# Clock_V1_0_0.net
KiCad netlist of a schematic drawn in EasyEDA Pro
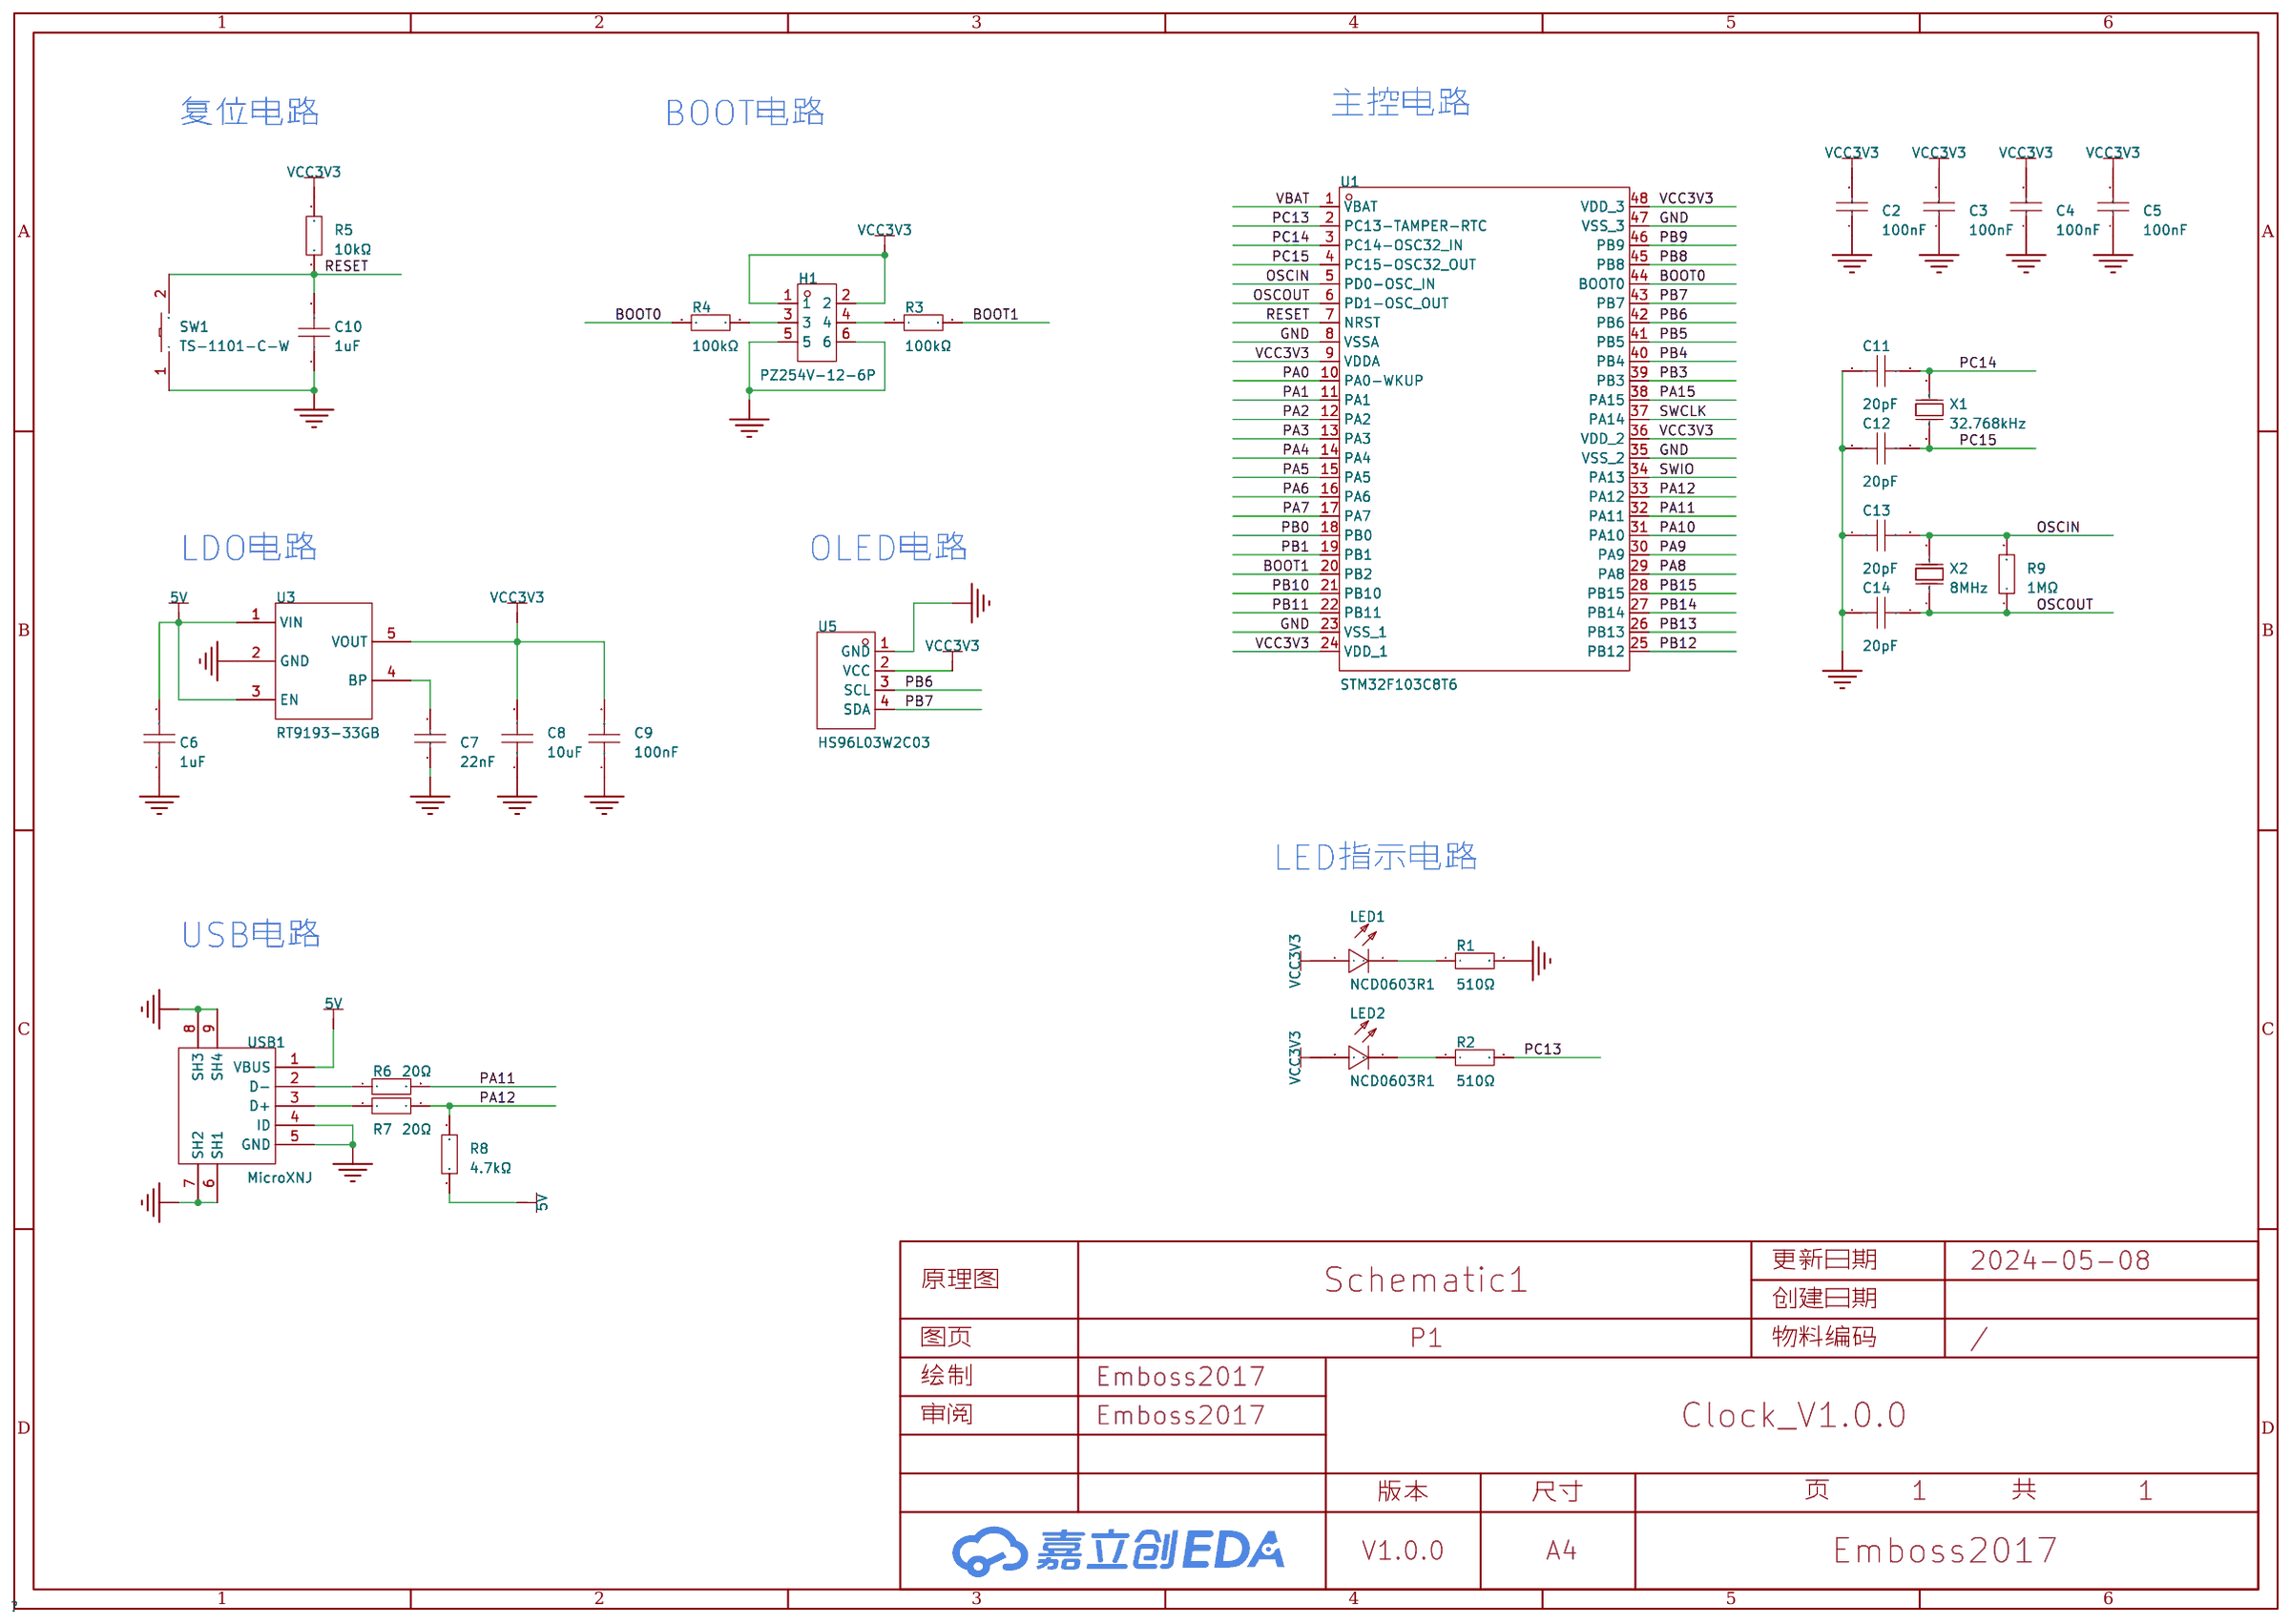
[diagram p0: schematic sheet]

(export (version "E")
  (design (tool "Eeschema 10.0.6"))
  (components
    (comp (ref "C2")
      (value "100nF")
      (footprint "easyedapro:C0603")
      (description "容值:100nF;精度:±10%;额定电压:50V;材质(温度系数):X7R;")
      (fields (field (name "Manufacturer Part") "0603B104K500NT") (field (name "Manufacturer") "FH(风华)"))
      (libsource (lib "easyedapro") (part "0603B104K500NT"))
    )
    (comp (ref "C3")
      (value "100nF")
      (footprint "easyedapro:C0603")
      (description "容值:100nF;精度:±10%;额定电压:50V;材质(温度系数):X7R;")
      (fields (field (name "Manufacturer Part") "0603B104K500NT") (field (name "Manufacturer") "FH(风华)"))
      (libsource (lib "easyedapro") (part "0603B104K500NT"))
    )
    (comp (ref "C4")
      (value "100nF")
      (footprint "easyedapro:C0603")
      (description "容值:100nF;精度:±10%;额定电压:50V;材质(温度系数):X7R;")
      (fields (field (name "Manufacturer Part") "0603B104K500NT") (field (name "Manufacturer") "FH(风华)"))
      (libsource (lib "easyedapro") (part "0603B104K500NT"))
    )
    (comp (ref "C5")
      (value "100nF")
      (footprint "easyedapro:C0603")
      (description "容值:100nF;精度:±10%;额定电压:50V;材质(温度系数):X7R;")
      (fields (field (name "Manufacturer Part") "0603B104K500NT") (field (name "Manufacturer") "FH(风华)"))
      (libsource (lib "easyedapro") (part "0603B104K500NT"))
    )
    (comp (ref "C6")
      (value "1uF")
      (footprint "easyedapro:C0603")
      (description "容值:-;额定电压:-;材质(温度系数):-;")
      (fields (field (name "Manufacturer Part") "1uF(105) ±10% 25V"))
      (libsource (lib "easyedapro") (part "1UF(105)-±10%-25V"))
    )
    (comp (ref "C7")
      (value "22nF")
      (footprint "easyedapro:C0603")
      (description "容值:22nF;精度:±10%;额定电压:50V;材质(温度系数):X7R;")
      (fields
        (field (name "Manufacturer Part") "CL10B223KB8NNNC")
        (field (name "Manufacturer") "SAMSUNG(三星)")
      )
      (libsource (lib "easyedapro") (part "CL10B223KB8NNNC"))
    )
    (comp (ref "C8")
      (value "10uF")
      (footprint "easyedapro:C0603")
      (description "容值:10uF;精度:±10%;额定电压:10V;材质(温度系数):X5R;")
      (fields
        (field (name "Manufacturer Part") "CL10A106KP8NNNC")
        (field (name "Manufacturer") "SAMSUNG(三星)")
      )
      (libsource (lib "easyedapro") (part "CL10A106KP8NNNC"))
    )
    (comp (ref "C9")
      (value "100nF")
      (footprint "easyedapro:C0603")
      (description "容值:100nF;精度:±10%;额定电压:50V;材质(温度系数):X7R;")
      (fields
        (field (name "Manufacturer Part") "CC0603KRX7R9BB104")
        (field (name "Manufacturer") "YAGEO(国巨)")
      )
      (libsource (lib "easyedapro") (part "CC0603KRX7R9BB104"))
    )
    (comp (ref "C10")
      (value "1uF")
      (footprint "easyedapro:C0603")
      (description "容值:-;额定电压:-;材质(温度系数):-;")
      (fields (field (name "Manufacturer Part") "1uF(105) ±10% 25V"))
      (libsource (lib "easyedapro") (part "1UF(105)-±10%-25V"))
    )
    (comp (ref "C11")
      (value "20pF")
      (footprint "easyedapro:C0603")
      (description "容值:20pF;精度:±5%;额定电压:50V;材质(温度系数):C0G;")
      (fields (field (name "Manufacturer Part") "0603CG200J500NT") (field (name "Manufacturer") "FH(风华)"))
      (libsource (lib "easyedapro") (part "0603CG200J500NT"))
    )
    (comp (ref "C12")
      (value "20pF")
      (footprint "easyedapro:C0603")
      (description "容值:20pF;精度:±5%;额定电压:50V;材质(温度系数):C0G;")
      (fields (field (name "Manufacturer Part") "0603CG200J500NT") (field (name "Manufacturer") "FH(风华)"))
      (libsource (lib "easyedapro") (part "0603CG200J500NT"))
    )
    (comp (ref "C13")
      (value "20pF")
      (footprint "easyedapro:C0603")
      (description "容值:20pF;精度:±5%;额定电压:50V;材质(温度系数):C0G;")
      (fields (field (name "Manufacturer Part") "0603CG200J500NT") (field (name "Manufacturer") "FH(风华)"))
      (libsource (lib "easyedapro") (part "0603CG200J500NT"))
    )
    (comp (ref "C14")
      (value "20pF")
      (footprint "easyedapro:C0603")
      (description "容值:20pF;精度:±5%;额定电压:50V;材质(温度系数):C0G;")
      (fields (field (name "Manufacturer Part") "0603CG200J500NT") (field (name "Manufacturer") "FH(风华)"))
      (libsource (lib "easyedapro") (part "0603CG200J500NT"))
    )
    (comp (ref "H1")
      (value "PZ254V-12-6P")
      (footprint "easyedapro:HDR-TH_6P-P2.54-V-M-R2-C3-S2.54")
      (fields (field (name "Manufacturer") "XFCN(兴飞)"))
      (libsource (lib "easyedapro") (part "PZ254V-12-6P"))
    )
    (comp (ref "LED1")
      (value "NCD0603R1")
      (footprint "easyedapro:LED0603-RD_RED")
      (fields (field (name "Manufacturer") "国星光电"))
      (libsource (lib "easyedapro") (part "FC-DA1608HRK-620D"))
    )
    (comp (ref "LED2")
      (value "NCD0603R1")
      (footprint "easyedapro:LED0603-RD_RED")
      (fields (field (name "Manufacturer") "国星光电"))
      (libsource (lib "easyedapro") (part "FC-DA1608HRK-620D"))
    )
    (comp (ref "R1")
      (value "510Ω")
      (footprint "easyedapro:R0603")
      (description "电阻类型:厚膜电阻;阻值:510Ω;精度:±1%;功率:100mW;最大工作电压:75V;温度系数:±100ppm/°C;")
      (fields
        (field (name "Manufacturer Part") "0603WAF5100T5E")
        (field (name "Manufacturer") "UNI-ROYAL(厚声)")
      )
      (libsource (lib "easyedapro") (part "0603WAF5100T5E"))
    )
    (comp (ref "R2")
      (value "510Ω")
      (footprint "easyedapro:R0603")
      (description "电阻类型:厚膜电阻;阻值:510Ω;精度:±1%;功率:100mW;最大工作电压:75V;温度系数:±100ppm/°C;")
      (fields
        (field (name "Manufacturer Part") "0603WAF5100T5E")
        (field (name "Manufacturer") "UNI-ROYAL(厚声)")
      )
      (libsource (lib "easyedapro") (part "0603WAF5100T5E"))
    )
    (comp (ref "R3")
      (value "100kΩ")
      (footprint "easyedapro:R0603")
      (description "电阻类型:厚膜电阻;阻值:100kΩ;精度:±1%;功率:100mW;最大工作电压:75V;温度系数:±100ppm/°C;")
      (fields
        (field (name "Manufacturer Part") "0603WAF1003T5E")
        (field (name "Manufacturer") "UNI-ROYAL(厚声)")
      )
      (libsource (lib "easyedapro") (part "0603WAF1003T5E"))
    )
    (comp (ref "R4")
      (value "100kΩ")
      (footprint "easyedapro:R0603")
      (description "电阻类型:厚膜电阻;阻值:100kΩ;精度:±1%;功率:100mW;最大工作电压:75V;温度系数:±100ppm/°C;")
      (fields
        (field (name "Manufacturer Part") "0603WAF1003T5E")
        (field (name "Manufacturer") "UNI-ROYAL(厚声)")
      )
      (libsource (lib "easyedapro") (part "0603WAF1003T5E"))
    )
    (comp (ref "R5")
      (value "10kΩ")
      (footprint "easyedapro:R0603")
      (description "电阻类型:厚膜电阻;阻值:10kΩ;精度:±1%;功率:100mW;最大工作电压:75V;温度系数:±100ppm/°C;")
      (fields
        (field (name "Manufacturer Part") "0603WAF1002T5E")
        (field (name "Manufacturer") "UNI-ROYAL(厚声)")
      )
      (libsource (lib "easyedapro") (part "0603WAF1002T5E"))
    )
    (comp (ref "R6")
      (value "20Ω")
      (footprint "easyedapro:R1206")
      (description "电阻类型:厚膜电阻;阻值:20Ω;精度:±1%;功率:250mW;最大工作电压:200V;温度系数:±100ppm/°C;")
      (fields
        (field (name "Manufacturer Part") "1206W4F200JT5E")
        (field (name "Manufacturer") "UNI-ROYAL(厚声)")
      )
      (libsource (lib "easyedapro") (part "1206W4F200JT5E"))
    )
    (comp (ref "R7")
      (value "20Ω")
      (footprint "easyedapro:R1206")
      (description "电阻类型:厚膜电阻;阻值:20Ω;精度:±1%;功率:250mW;最大工作电压:200V;温度系数:±100ppm/°C;")
      (fields
        (field (name "Manufacturer Part") "1206W4F200JT5E")
        (field (name "Manufacturer") "UNI-ROYAL(厚声)")
      )
      (libsource (lib "easyedapro") (part "1206W4F200JT5E"))
    )
    (comp (ref "R8")
      (value "4.7kΩ")
      (footprint "easyedapro:R0603")
      (description "电阻类型:厚膜电阻;阻值:4.7kΩ;精度:±1%;功率:100mW;最大工作电压:75V;温度系数:±100ppm/°C;")
      (fields
        (field (name "Manufacturer Part") "0603WAF4701T5E")
        (field (name "Manufacturer") "UNI-ROYAL(厚声)")
      )
      (libsource (lib "easyedapro") (part "0603WAF4701T5E"))
    )
    (comp (ref "R9")
      (value "1MΩ")
      (footprint "easyedapro:R0603")
      (description "电阻类型:厚膜电阻;阻值:1MΩ;精度:±1%;功率:100mW;最大工作电压:75V;温度系数:±100ppm/°C;")
      (fields
        (field (name "Manufacturer Part") "0603WAF1004T5E")
        (field (name "Manufacturer") "UNI-ROYAL(厚声)")
      )
      (libsource (lib "easyedapro") (part "0603WAF1004T5E"))
    )
    (comp (ref "SW1")
      (value "TS-1101-C-W")
      (footprint "easyedapro:SW-SMD_L6.0-W3.3-LS8.0")
      (fields (field (name "Manufacturer") "XKB Connectivity(中国星坤)"))
      (libsource (lib "easyedapro") (part "TS-1101-C-W"))
    )
    (comp (ref "U1")
      (value "STM32F103C8T6")
      (footprint "easyedapro:LQFP-48_L7.0-W7.0-P0.50-LS9.0-BL")
      (description "CPU内核:CM3;程序存储容量:64KB;RAM总容量:20KB;GPIO端口数量:37;工作电压范围:2V~3.6V;CPU最大主频:72MHz;程序存储器类型:FLASH;")
      (fields (field (name "Manufacturer") "ST(意法半导体)"))
      (libsource (lib "easyedapro") (part "STM32F103C8T6"))
    )
    (comp (ref "U3")
      (value "RT9193-33GB")
      (footprint "easyedapro:SOT-23-5_L3.0-W1.7-P0.95-LS2.8-BL")
      (description "输出类型:固定;最大输入电压:5.5V;输出电压:3.3V;最大输出电流:300mA;电源纹波抑制比(PSRR):70dB;输出极性:正极;")
      (fields (field (name "Manufacturer") "RICHTEK(立锜)"))
      (libsource (lib "easyedapro") (part "RT9193-33GB"))
    )
    (comp (ref "U5")
      (value "HS96L03W2C03")
      (footprint "easyedapro:OLED-TH_L27.8-W27.2-P2.54_C9900033791")
      (description "主控芯片:SSD1315;接口类型:I2C;尺寸(inch):0.96;像素分辨率:128x64;")
      (fields (field (name "Manufacturer") "HS(汉昇)"))
      (libsource (lib "easyedapro") (part "HS96L03W2C03"))
    )
    (comp (ref "USB1")
      (value "MicroXNJ")
      (footprint "easyedapro:MICRO-USB-SMD_MICROXNJ")
      (description "连接器类型:Micro-B;标准:USB 2.0;公母:母;端口数量:1;触点数量:5P;安装方式:卧贴;额定电流 - 电源:1A;工作温度范围:-20°C~+85°C;")
      (fields (field (name "Manufacturer") "SHOU HAN(首韩)"))
      (libsource (lib "easyedapro") (part "MICROXNJ"))
    )
    (comp (ref "X1")
      (value "32.768kHz")
      (footprint "easyedapro:OSC-TH_BD2.0-P0.70-D0.3")
      (description "晶振类型:-;频率:-;外接负载电容:-;")
      (fields (field (name "Manufacturer Part") "DT-26 32.768KHz") (field (name "Manufacturer") "KDS(大真空)"))
      (libsource (lib "easyedapro") (part "DT-26 32.768KHz"))
    )
    (comp (ref "X2")
      (value "8MHz")
      (footprint "easyedapro:CRYSTAL-SMD_L11.5-W4.8-LS12.7")
      (description "晶振类型:贴片晶振;频率:8MHz;常温频差:±20ppm;外接负载电容:20pF;频率稳定度(全温):±30ppm;")
      (fields (field (name "Manufacturer Part") "X49SM8MSD2SC") (field (name "Manufacturer") "YXC(扬兴晶振)"))
      (libsource (lib "easyedapro") (part "X49SM8MSD2SC"))
    )
  )
  (nets
    (net (code "1") (name "/BOOT0") (class "Default")
      (node (ref "R4") (pin "1") (pinfunction "1_1") (pintype "input"))
      (node (ref "U1") (pin "44") (pinfunction "BOOT0_44") (pintype "unspecified"))
    )
    (net (code "2") (name "/BOOT1") (class "Default")
      (node (ref "R3") (pin "2") (pinfunction "2_2") (pintype "input"))
      (node (ref "U1") (pin "20") (pinfunction "PB2_20") (pintype "unspecified"))
    )
    (net (code "3") (name "/OSCIN") (class "Default")
      (node (ref "C13") (pin "2") (pinfunction "2_2") (pintype "unspecified"))
      (node (ref "R9") (pin "2") (pinfunction "2_2") (pintype "input"))
      (node (ref "U1") (pin "5") (pinfunction "PD0-OSC_IN_5") (pintype "unspecified"))
      (node (ref "X2") (pin "2") (pinfunction "OSC2_2") (pintype "input"))
    )
    (net (code "4") (name "/OSCOUT") (class "Default")
      (node (ref "C14") (pin "2") (pinfunction "2_2") (pintype "unspecified"))
      (node (ref "R9") (pin "1") (pinfunction "1_1") (pintype "input"))
      (node (ref "U1") (pin "6") (pinfunction "PD1-OSC_OUT_6") (pintype "unspecified"))
      (node (ref "X2") (pin "1") (pinfunction "OSC1_1") (pintype "input"))
    )
    (net (code "5") (name "/PA0") (class "Default")
      (node (ref "U1") (pin "10") (pinfunction "PA0-WKUP_10") (pintype "unspecified"))
    )
    (net (code "6") (name "/PA1") (class "Default")
      (node (ref "U1") (pin "11") (pinfunction "PA1_11") (pintype "unspecified"))
    )
    (net (code "7") (name "/PA2") (class "Default")
      (node (ref "U1") (pin "12") (pinfunction "PA2_12") (pintype "unspecified"))
    )
    (net (code "8") (name "/PA3") (class "Default")
      (node (ref "U1") (pin "13") (pinfunction "PA3_13") (pintype "unspecified"))
    )
    (net (code "9") (name "/PA4") (class "Default")
      (node (ref "U1") (pin "14") (pinfunction "PA4_14") (pintype "unspecified"))
    )
    (net (code "10") (name "/PA5") (class "Default")
      (node (ref "U1") (pin "15") (pinfunction "PA5_15") (pintype "unspecified"))
    )
    (net (code "11") (name "/PA6") (class "Default")
      (node (ref "U1") (pin "16") (pinfunction "PA6_16") (pintype "unspecified"))
    )
    (net (code "12") (name "/PA7") (class "Default")
      (node (ref "U1") (pin "17") (pinfunction "PA7_17") (pintype "unspecified"))
    )
    (net (code "13") (name "/PA8") (class "Default")
      (node (ref "U1") (pin "29") (pinfunction "PA8_29") (pintype "unspecified"))
    )
    (net (code "14") (name "/PA9") (class "Default")
      (node (ref "U1") (pin "30") (pinfunction "PA9_30") (pintype "unspecified"))
    )
    (net (code "15") (name "/PA10") (class "Default")
      (node (ref "U1") (pin "31") (pinfunction "PA10_31") (pintype "unspecified"))
    )
    (net (code "16") (name "/PA11") (class "Default")
      (node (ref "R6") (pin "2") (pinfunction "2_2") (pintype "input"))
      (node (ref "U1") (pin "32") (pinfunction "PA11_32") (pintype "unspecified"))
    )
    (net (code "17") (name "/PA12") (class "Default")
      (node (ref "R7") (pin "2") (pinfunction "2_2") (pintype "input"))
      (node (ref "R8") (pin "2") (pinfunction "2_2") (pintype "input"))
      (node (ref "U1") (pin "33") (pinfunction "PA12_33") (pintype "unspecified"))
    )
    (net (code "18") (name "/PA15") (class "Default")
      (node (ref "U1") (pin "38") (pinfunction "PA15_38") (pintype "unspecified"))
    )
    (net (code "19") (name "/PB0") (class "Default")
      (node (ref "U1") (pin "18") (pinfunction "PB0_18") (pintype "unspecified"))
    )
    (net (code "20") (name "/PB1") (class "Default")
      (node (ref "U1") (pin "19") (pinfunction "PB1_19") (pintype "unspecified"))
    )
    (net (code "21") (name "/PB3") (class "Default")
      (node (ref "U1") (pin "39") (pinfunction "PB3_39") (pintype "unspecified"))
    )
    (net (code "22") (name "/PB4") (class "Default")
      (node (ref "U1") (pin "40") (pinfunction "PB4_40") (pintype "unspecified"))
    )
    (net (code "23") (name "/PB5") (class "Default")
      (node (ref "U1") (pin "41") (pinfunction "PB5_41") (pintype "unspecified"))
    )
    (net (code "24") (name "/PB6") (class "Default")
      (node (ref "U1") (pin "42") (pinfunction "PB6_42") (pintype "unspecified"))
      (node (ref "U5") (pin "3") (pinfunction "SCL_3") (pintype "unspecified"))
    )
    (net (code "25") (name "/PB7") (class "Default")
      (node (ref "U1") (pin "43") (pinfunction "PB7_43") (pintype "unspecified"))
      (node (ref "U5") (pin "4") (pinfunction "SDA_4") (pintype "unspecified"))
    )
    (net (code "26") (name "/PB8") (class "Default")
      (node (ref "U1") (pin "45") (pinfunction "PB8_45") (pintype "unspecified"))
    )
    (net (code "27") (name "/PB9") (class "Default")
      (node (ref "U1") (pin "46") (pinfunction "PB9_46") (pintype "unspecified"))
    )
    (net (code "28") (name "/PB10") (class "Default")
      (node (ref "U1") (pin "21") (pinfunction "PB10_21") (pintype "unspecified"))
    )
    (net (code "29") (name "/PB11") (class "Default")
      (node (ref "U1") (pin "22") (pinfunction "PB11_22") (pintype "unspecified"))
    )
    (net (code "30") (name "/PB12") (class "Default")
      (node (ref "U1") (pin "25") (pinfunction "PB12_25") (pintype "unspecified"))
    )
    (net (code "31") (name "/PB13") (class "Default")
      (node (ref "U1") (pin "26") (pinfunction "PB13_26") (pintype "unspecified"))
    )
    (net (code "32") (name "/PB14") (class "Default")
      (node (ref "U1") (pin "27") (pinfunction "PB14_27") (pintype "unspecified"))
    )
    (net (code "33") (name "/PB15") (class "Default")
      (node (ref "U1") (pin "28") (pinfunction "PB15_28") (pintype "unspecified"))
    )
    (net (code "34") (name "/PC13") (class "Default")
      (node (ref "R2") (pin "2") (pinfunction "2_2") (pintype "input"))
      (node (ref "U1") (pin "2") (pinfunction "PC13-TAMPER-RTC_2") (pintype "unspecified"))
    )
    (net (code "35") (name "/PC14") (class "Default")
      (node (ref "C11") (pin "2") (pinfunction "2_2") (pintype "unspecified"))
      (node (ref "U1") (pin "3") (pinfunction "PC14-OSC32_IN_3") (pintype "unspecified"))
      (node (ref "X1") (pin "1") (pinfunction "OSC1_1") (pintype "input"))
    )
    (net (code "36") (name "/PC15") (class "Default")
      (node (ref "C12") (pin "2") (pinfunction "2_2") (pintype "unspecified"))
      (node (ref "U1") (pin "4") (pinfunction "PC15-OSC32_OUT_4") (pintype "unspecified"))
      (node (ref "X1") (pin "2") (pinfunction "OSC2_2") (pintype "input"))
    )
    (net (code "37") (name "/RESET") (class "Default")
      (node (ref "C10") (pin "2") (pinfunction "2_2") (pintype "input"))
      (node (ref "R5") (pin "1") (pinfunction "1_1") (pintype "input"))
      (node (ref "SW1") (pin "2") (pinfunction "2_2") (pintype "unspecified"))
      (node (ref "U1") (pin "7") (pinfunction "NRST_7") (pintype "unspecified"))
    )
    (net (code "38") (name "/SWCLK") (class "Default")
      (node (ref "U1") (pin "37") (pinfunction "PA14_37") (pintype "unspecified"))
    )
    (net (code "39") (name "/SWIO") (class "Default")
      (node (ref "U1") (pin "34") (pinfunction "PA13_34") (pintype "unspecified"))
    )
    (net (code "40") (name "/VBAT") (class "Default")
      (node (ref "U1") (pin "1") (pinfunction "VBAT_1") (pintype "unspecified"))
    )
    (net (code "41") (name "5V") (class "Default")
      (node (ref "C6") (pin "2") (pinfunction "2_2") (pintype "input"))
      (node (ref "R8") (pin "1") (pinfunction "1_1") (pintype "input"))
      (node (ref "U3") (pin "1") (pinfunction "VIN_1") (pintype "unspecified"))
      (node (ref "U3") (pin "3") (pinfunction "EN_3") (pintype "unspecified"))
      (node (ref "USB1") (pin "1") (pinfunction "VBUS_1") (pintype "unspecified"))
    )
    (net (code "42") (name "GND") (class "Default")
      (node (ref "C10") (pin "1") (pinfunction "1_1") (pintype "input"))
      (node (ref "C11") (pin "1") (pinfunction "1_1") (pintype "unspecified"))
      (node (ref "C12") (pin "1") (pinfunction "1_1") (pintype "unspecified"))
      (node (ref "C13") (pin "1") (pinfunction "1_1") (pintype "unspecified"))
      (node (ref "C14") (pin "1") (pinfunction "1_1") (pintype "unspecified"))
      (node (ref "C2") (pin "1") (pinfunction "1_1") (pintype "input"))
      (node (ref "C3") (pin "1") (pinfunction "1_1") (pintype "input"))
      (node (ref "C4") (pin "1") (pinfunction "1_1") (pintype "input"))
      (node (ref "C5") (pin "1") (pinfunction "1_1") (pintype "input"))
      (node (ref "C6") (pin "1") (pinfunction "1_1") (pintype "input"))
      (node (ref "C7") (pin "1") (pinfunction "1_1") (pintype "input"))
      (node (ref "C8") (pin "1") (pinfunction "1_1") (pintype "unspecified"))
      (node (ref "C9") (pin "1") (pinfunction "1_1") (pintype "unspecified"))
      (node (ref "H1") (pin "5") (pinfunction "5_5") (pintype "unspecified"))
      (node (ref "H1") (pin "6") (pinfunction "6_6") (pintype "unspecified"))
      (node (ref "R1") (pin "2") (pinfunction "2_2") (pintype "input"))
      (node (ref "SW1") (pin "1") (pinfunction "1_1") (pintype "unspecified"))
      (node (ref "U1") (pin "23") (pinfunction "VSS_1_23") (pintype "unspecified"))
      (node (ref "U1") (pin "35") (pinfunction "VSS_2_35") (pintype "unspecified"))
      (node (ref "U1") (pin "47") (pinfunction "VSS_3_47") (pintype "unspecified"))
      (node (ref "U1") (pin "8") (pinfunction "VSSA_8") (pintype "unspecified"))
      (node (ref "U3") (pin "2") (pinfunction "GND_2") (pintype "unspecified"))
      (node (ref "U5") (pin "1") (pinfunction "GND_1") (pintype "unspecified"))
      (node (ref "USB1") (pin "4") (pinfunction "ID_4") (pintype "unspecified"))
      (node (ref "USB1") (pin "5") (pinfunction "GND_5") (pintype "unspecified"))
      (node (ref "USB1") (pin "6") (pinfunction "SH1_6") (pintype "unspecified"))
      (node (ref "USB1") (pin "7") (pinfunction "SH2_7") (pintype "unspecified"))
      (node (ref "USB1") (pin "8") (pinfunction "SH3_8") (pintype "unspecified"))
      (node (ref "USB1") (pin "9") (pinfunction "SH4_9") (pintype "unspecified"))
    )
    (net (code "43") (name "Net-(H1-Pad3)") (class "Default")
      (node (ref "H1") (pin "3") (pinfunction "3_3") (pintype "unspecified"))
      (node (ref "R4") (pin "2") (pinfunction "2_2") (pintype "input"))
    )
    (net (code "44") (name "Net-(H1-Pad4)") (class "Default")
      (node (ref "H1") (pin "4") (pinfunction "4_4") (pintype "unspecified"))
      (node (ref "R3") (pin "1") (pinfunction "1_1") (pintype "input"))
    )
    (net (code "45") (name "Net-(LED1-K)") (class "Default")
      (node (ref "LED1") (pin "1") (pinfunction "K_1") (pintype "input"))
      (node (ref "R1") (pin "1") (pinfunction "1_1") (pintype "input"))
    )
    (net (code "46") (name "Net-(LED2-K)") (class "Default")
      (node (ref "LED2") (pin "1") (pinfunction "K_1") (pintype "input"))
      (node (ref "R2") (pin "1") (pinfunction "1_1") (pintype "input"))
    )
    (net (code "47") (name "Net-(U3-BP)") (class "Default")
      (node (ref "C7") (pin "2") (pinfunction "2_2") (pintype "input"))
      (node (ref "U3") (pin "4") (pinfunction "BP_4") (pintype "unspecified"))
    )
    (net (code "48") (name "Net-(USB1-D+)") (class "Default")
      (node (ref "R7") (pin "1") (pinfunction "1_1") (pintype "input"))
      (node (ref "USB1") (pin "3") (pinfunction "D+_3") (pintype "unspecified"))
    )
    (net (code "49") (name "Net-(USB1-D-)") (class "Default")
      (node (ref "R6") (pin "1") (pinfunction "1_1") (pintype "input"))
      (node (ref "USB1") (pin "2") (pinfunction "D-_2") (pintype "unspecified"))
    )
    (net (code "50") (name "VCC3V3") (class "Default")
      (node (ref "C2") (pin "2") (pinfunction "2_2") (pintype "input"))
      (node (ref "C3") (pin "2") (pinfunction "2_2") (pintype "input"))
      (node (ref "C4") (pin "2") (pinfunction "2_2") (pintype "input"))
      (node (ref "C5") (pin "2") (pinfunction "2_2") (pintype "input"))
      (node (ref "C8") (pin "2") (pinfunction "2_2") (pintype "unspecified"))
      (node (ref "C9") (pin "2") (pinfunction "2_2") (pintype "unspecified"))
      (node (ref "H1") (pin "1") (pinfunction "1_1") (pintype "unspecified"))
      (node (ref "H1") (pin "2") (pinfunction "2_2") (pintype "unspecified"))
      (node (ref "LED1") (pin "2") (pinfunction "A_2") (pintype "input"))
      (node (ref "LED2") (pin "2") (pinfunction "A_2") (pintype "input"))
      (node (ref "R5") (pin "2") (pinfunction "2_2") (pintype "input"))
      (node (ref "U1") (pin "24") (pinfunction "VDD_1_24") (pintype "unspecified"))
      (node (ref "U1") (pin "36") (pinfunction "VDD_2_36") (pintype "unspecified"))
      (node (ref "U1") (pin "48") (pinfunction "VDD_3_48") (pintype "unspecified"))
      (node (ref "U1") (pin "9") (pinfunction "VDDA_9") (pintype "unspecified"))
      (node (ref "U3") (pin "5") (pinfunction "VOUT_5") (pintype "unspecified"))
      (node (ref "U5") (pin "2") (pinfunction "VCC_2") (pintype "unspecified"))
    )
  )
)
